# LEDStrip.net
KiCad netlist of a schematic drawn in EAGLE
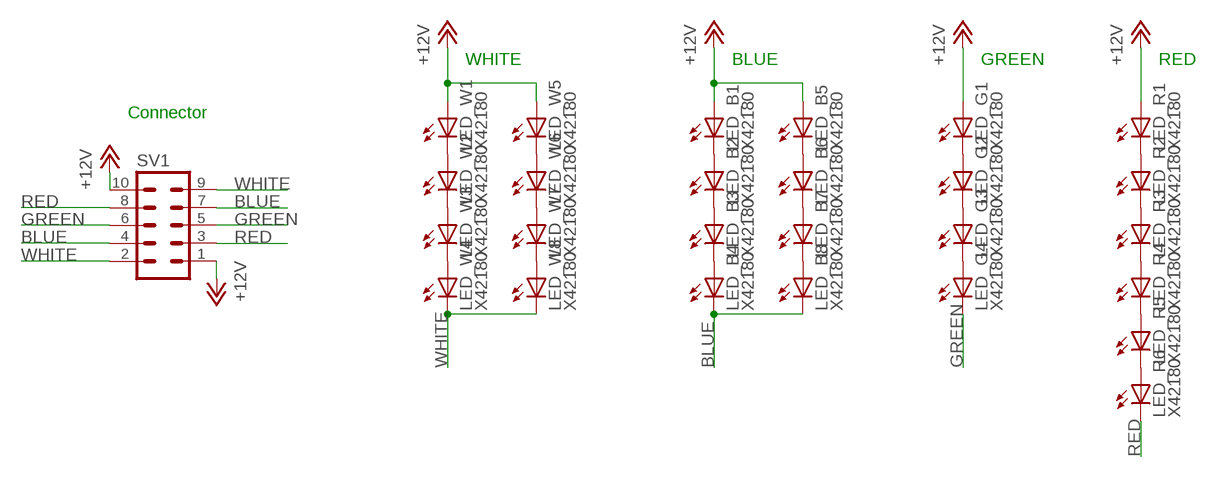
[diagram p0: schematic, sheet 1]

(export (version "E")
  (design (tool "Eeschema 10.0.6"))
  (components
    (comp (ref "LED_B1")
      (value "X42180")
      (footprint "eagle-import:Z-POWER-LED-DOME-TYPE")
      (libsource (lib "eagle-import") (part "X42180"))
    )
    (comp (ref "LED_B2")
      (value "X42180")
      (footprint "eagle-import:Z-POWER-LED-DOME-TYPE")
      (libsource (lib "eagle-import") (part "X42180"))
    )
    (comp (ref "LED_B3")
      (value "X42180")
      (footprint "eagle-import:Z-POWER-LED-DOME-TYPE")
      (libsource (lib "eagle-import") (part "X42180"))
    )
    (comp (ref "LED_B4")
      (value "X42180")
      (footprint "eagle-import:Z-POWER-LED-DOME-TYPE")
      (libsource (lib "eagle-import") (part "X42180"))
    )
    (comp (ref "LED_B5")
      (value "X42180")
      (footprint "eagle-import:Z-POWER-LED-DOME-TYPE")
      (libsource (lib "eagle-import") (part "X42180"))
    )
    (comp (ref "LED_B6")
      (value "X42180")
      (footprint "eagle-import:Z-POWER-LED-DOME-TYPE")
      (libsource (lib "eagle-import") (part "X42180"))
    )
    (comp (ref "LED_B7")
      (value "X42180")
      (footprint "eagle-import:Z-POWER-LED-DOME-TYPE")
      (libsource (lib "eagle-import") (part "X42180"))
    )
    (comp (ref "LED_B8")
      (value "X42180")
      (footprint "eagle-import:Z-POWER-LED-DOME-TYPE")
      (libsource (lib "eagle-import") (part "X42180"))
    )
    (comp (ref "LED_G1")
      (value "X42180")
      (footprint "eagle-import:Z-POWER-LED-DOME-TYPE")
      (libsource (lib "eagle-import") (part "X42180"))
    )
    (comp (ref "LED_G2")
      (value "X42180")
      (footprint "eagle-import:Z-POWER-LED-DOME-TYPE")
      (libsource (lib "eagle-import") (part "X42180"))
    )
    (comp (ref "LED_G3")
      (value "X42180")
      (footprint "eagle-import:Z-POWER-LED-DOME-TYPE")
      (libsource (lib "eagle-import") (part "X42180"))
    )
    (comp (ref "LED_G4")
      (value "X42180")
      (footprint "eagle-import:Z-POWER-LED-DOME-TYPE")
      (libsource (lib "eagle-import") (part "X42180"))
    )
    (comp (ref "LED_R1")
      (value "X42180")
      (footprint "eagle-import:Z-POWER-LED-DOME-TYPE")
      (libsource (lib "eagle-import") (part "X42180"))
    )
    (comp (ref "LED_R2")
      (value "X42180")
      (footprint "eagle-import:Z-POWER-LED-DOME-TYPE")
      (libsource (lib "eagle-import") (part "X42180"))
    )
    (comp (ref "LED_R3")
      (value "X42180")
      (footprint "eagle-import:Z-POWER-LED-DOME-TYPE")
      (libsource (lib "eagle-import") (part "X42180"))
    )
    (comp (ref "LED_R4")
      (value "X42180")
      (footprint "eagle-import:Z-POWER-LED-DOME-TYPE")
      (libsource (lib "eagle-import") (part "X42180"))
    )
    (comp (ref "LED_R5")
      (value "X42180")
      (footprint "eagle-import:Z-POWER-LED-DOME-TYPE")
      (libsource (lib "eagle-import") (part "X42180"))
    )
    (comp (ref "LED_R6")
      (value "X42180")
      (footprint "eagle-import:Z-POWER-LED-DOME-TYPE")
      (libsource (lib "eagle-import") (part "X42180"))
    )
    (comp (ref "LED_W1")
      (value "X42180")
      (footprint "eagle-import:Z-POWER-LED-DOME-TYPE")
      (libsource (lib "eagle-import") (part "X42180"))
    )
    (comp (ref "LED_W2")
      (value "X42180")
      (footprint "eagle-import:Z-POWER-LED-DOME-TYPE")
      (libsource (lib "eagle-import") (part "X42180"))
    )
    (comp (ref "LED_W3")
      (value "X42180")
      (footprint "eagle-import:Z-POWER-LED-DOME-TYPE")
      (libsource (lib "eagle-import") (part "X42180"))
    )
    (comp (ref "LED_W4")
      (value "X42180")
      (footprint "eagle-import:Z-POWER-LED-DOME-TYPE")
      (libsource (lib "eagle-import") (part "X42180"))
    )
    (comp (ref "LED_W5")
      (value "X42180")
      (footprint "eagle-import:Z-POWER-LED-DOME-TYPE")
      (libsource (lib "eagle-import") (part "X42180"))
    )
    (comp (ref "LED_W6")
      (value "X42180")
      (footprint "eagle-import:Z-POWER-LED-DOME-TYPE")
      (libsource (lib "eagle-import") (part "X42180"))
    )
    (comp (ref "LED_W7")
      (value "X42180")
      (footprint "eagle-import:Z-POWER-LED-DOME-TYPE")
      (libsource (lib "eagle-import") (part "X42180"))
    )
    (comp (ref "LED_W8")
      (value "X42180")
      (footprint "eagle-import:Z-POWER-LED-DOME-TYPE")
      (libsource (lib "eagle-import") (part "X42180"))
    )
    (comp (ref "SV1")
      (value "MA05-2")
      (footprint "eagle-import:MA05-2")
      (libsource (lib "eagle-import") (part "MA05-2"))
    )
  )
  (nets
    (net (code "1") (name "+12V") (class "Default")
      (node (ref "LED_B1") (pin "A") (pinfunction "A_A") (pintype "passive"))
      (node (ref "LED_B5") (pin "A") (pinfunction "A_A") (pintype "passive"))
      (node (ref "LED_G1") (pin "A") (pinfunction "A_A") (pintype "passive"))
      (node (ref "LED_R1") (pin "A") (pinfunction "A_A") (pintype "passive"))
      (node (ref "LED_W1") (pin "A") (pinfunction "A_A") (pintype "passive"))
      (node (ref "LED_W5") (pin "A") (pinfunction "A_A") (pintype "passive"))
      (node (ref "SV1") (pin "1") (pinfunction "1_1") (pintype "passive"))
      (node (ref "SV1") (pin "10") (pinfunction "10_10") (pintype "passive"))
    )
    (net (code "2") (name "/BLUE") (class "Default")
      (node (ref "LED_B4") (pin "C") (pinfunction "C_C") (pintype "passive"))
      (node (ref "LED_B8") (pin "C") (pinfunction "C_C") (pintype "passive"))
      (node (ref "SV1") (pin "4") (pinfunction "4_4") (pintype "passive"))
      (node (ref "SV1") (pin "7") (pinfunction "7_7") (pintype "passive"))
    )
    (net (code "3") (name "/GREEN") (class "Default")
      (node (ref "LED_G4") (pin "C") (pinfunction "C_C") (pintype "passive"))
      (node (ref "SV1") (pin "5") (pinfunction "5_5") (pintype "passive"))
      (node (ref "SV1") (pin "6") (pinfunction "6_6") (pintype "passive"))
    )
    (net (code "4") (name "/RED") (class "Default")
      (node (ref "LED_R6") (pin "C") (pinfunction "C_C") (pintype "passive"))
      (node (ref "SV1") (pin "3") (pinfunction "3_3") (pintype "passive"))
      (node (ref "SV1") (pin "8") (pinfunction "8_8") (pintype "passive"))
    )
    (net (code "5") (name "/WHITE") (class "Default")
      (node (ref "LED_W4") (pin "C") (pinfunction "C_C") (pintype "passive"))
      (node (ref "LED_W8") (pin "C") (pinfunction "C_C") (pintype "passive"))
      (node (ref "SV1") (pin "2") (pinfunction "2_2") (pintype "passive"))
      (node (ref "SV1") (pin "9") (pinfunction "9_9") (pintype "passive"))
    )
    (net (code "6") (name "Net-(LED_B1-PadC)") (class "Default")
      (node (ref "LED_B1") (pin "C") (pinfunction "C_C") (pintype "passive"))
      (node (ref "LED_B2") (pin "A") (pinfunction "A_A") (pintype "passive"))
    )
    (net (code "7") (name "Net-(LED_B2-PadC)") (class "Default")
      (node (ref "LED_B2") (pin "C") (pinfunction "C_C") (pintype "passive"))
      (node (ref "LED_B3") (pin "A") (pinfunction "A_A") (pintype "passive"))
    )
    (net (code "8") (name "Net-(LED_B3-PadC)") (class "Default")
      (node (ref "LED_B3") (pin "C") (pinfunction "C_C") (pintype "passive"))
      (node (ref "LED_B4") (pin "A") (pinfunction "A_A") (pintype "passive"))
    )
    (net (code "9") (name "Net-(LED_B5-PadC)") (class "Default")
      (node (ref "LED_B5") (pin "C") (pinfunction "C_C") (pintype "passive"))
      (node (ref "LED_B6") (pin "A") (pinfunction "A_A") (pintype "passive"))
    )
    (net (code "10") (name "Net-(LED_B6-PadC)") (class "Default")
      (node (ref "LED_B6") (pin "C") (pinfunction "C_C") (pintype "passive"))
      (node (ref "LED_B7") (pin "A") (pinfunction "A_A") (pintype "passive"))
    )
    (net (code "11") (name "Net-(LED_B7-PadC)") (class "Default")
      (node (ref "LED_B7") (pin "C") (pinfunction "C_C") (pintype "passive"))
      (node (ref "LED_B8") (pin "A") (pinfunction "A_A") (pintype "passive"))
    )
    (net (code "12") (name "Net-(LED_G1-PadC)") (class "Default")
      (node (ref "LED_G1") (pin "C") (pinfunction "C_C") (pintype "passive"))
      (node (ref "LED_G2") (pin "A") (pinfunction "A_A") (pintype "passive"))
    )
    (net (code "13") (name "Net-(LED_G2-PadC)") (class "Default")
      (node (ref "LED_G2") (pin "C") (pinfunction "C_C") (pintype "passive"))
      (node (ref "LED_G3") (pin "A") (pinfunction "A_A") (pintype "passive"))
    )
    (net (code "14") (name "Net-(LED_G3-PadC)") (class "Default")
      (node (ref "LED_G3") (pin "C") (pinfunction "C_C") (pintype "passive"))
      (node (ref "LED_G4") (pin "A") (pinfunction "A_A") (pintype "passive"))
    )
    (net (code "15") (name "Net-(LED_R1-PadC)") (class "Default")
      (node (ref "LED_R1") (pin "C") (pinfunction "C_C") (pintype "passive"))
      (node (ref "LED_R2") (pin "A") (pinfunction "A_A") (pintype "passive"))
    )
    (net (code "16") (name "Net-(LED_R2-PadC)") (class "Default")
      (node (ref "LED_R2") (pin "C") (pinfunction "C_C") (pintype "passive"))
      (node (ref "LED_R3") (pin "A") (pinfunction "A_A") (pintype "passive"))
    )
    (net (code "17") (name "Net-(LED_R3-PadC)") (class "Default")
      (node (ref "LED_R3") (pin "C") (pinfunction "C_C") (pintype "passive"))
      (node (ref "LED_R4") (pin "A") (pinfunction "A_A") (pintype "passive"))
    )
    (net (code "18") (name "Net-(LED_R4-PadC)") (class "Default")
      (node (ref "LED_R4") (pin "C") (pinfunction "C_C") (pintype "passive"))
      (node (ref "LED_R5") (pin "A") (pinfunction "A_A") (pintype "passive"))
    )
    (net (code "19") (name "Net-(LED_R5-PadC)") (class "Default")
      (node (ref "LED_R5") (pin "C") (pinfunction "C_C") (pintype "passive"))
      (node (ref "LED_R6") (pin "A") (pinfunction "A_A") (pintype "passive"))
    )
    (net (code "20") (name "Net-(LED_W1-PadC)") (class "Default")
      (node (ref "LED_W1") (pin "C") (pinfunction "C_C") (pintype "passive"))
      (node (ref "LED_W2") (pin "A") (pinfunction "A_A") (pintype "passive"))
    )
    (net (code "21") (name "Net-(LED_W2-PadC)") (class "Default")
      (node (ref "LED_W2") (pin "C") (pinfunction "C_C") (pintype "passive"))
      (node (ref "LED_W3") (pin "A") (pinfunction "A_A") (pintype "passive"))
    )
    (net (code "22") (name "Net-(LED_W3-PadC)") (class "Default")
      (node (ref "LED_W3") (pin "C") (pinfunction "C_C") (pintype "passive"))
      (node (ref "LED_W4") (pin "A") (pinfunction "A_A") (pintype "passive"))
    )
    (net (code "23") (name "Net-(LED_W5-PadC)") (class "Default")
      (node (ref "LED_W5") (pin "C") (pinfunction "C_C") (pintype "passive"))
      (node (ref "LED_W6") (pin "A") (pinfunction "A_A") (pintype "passive"))
    )
    (net (code "24") (name "Net-(LED_W6-PadC)") (class "Default")
      (node (ref "LED_W6") (pin "C") (pinfunction "C_C") (pintype "passive"))
      (node (ref "LED_W7") (pin "A") (pinfunction "A_A") (pintype "passive"))
    )
    (net (code "25") (name "Net-(LED_W7-PadC)") (class "Default")
      (node (ref "LED_W7") (pin "C") (pinfunction "C_C") (pintype "passive"))
      (node (ref "LED_W8") (pin "A") (pinfunction "A_A") (pintype "passive"))
    )
  )
)
